# TactSwitch_v2_SCH.net
KiCad netlist of a schematic drawn in Altium Designer
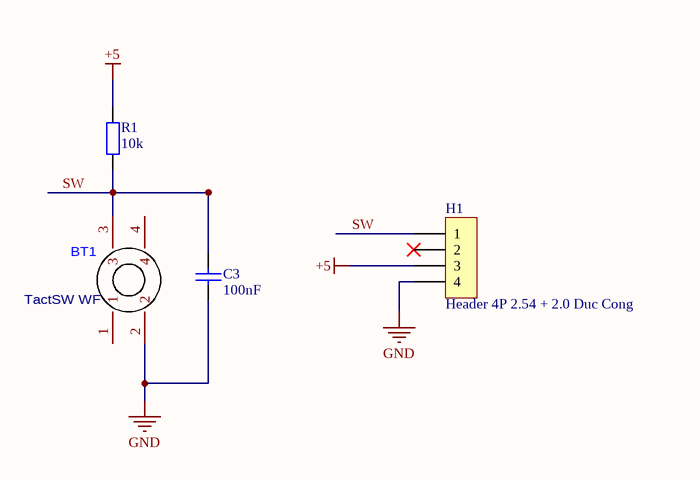
[diagram p0: TactSwitch_v2_SCH.SchDoc]

(export (version "E")
  (design (tool "Eeschema 10.0.6"))
  (components
    (comp (ref "BT1")
      (value "TactSW WF")
      (footprint "12X12 BUTTOM red")
      (description "WaterProof TactSW")
      (libsource (lib "namnt_Lib") (part "Nut Nhan 4 chan 12x12"))
    )
    (comp (ref "C3")
      (value "100nF")
      (footprint "tu 0603")
      (description "Dán")
      (libsource (lib "namnt_Lib") (part "Tu 0603 104 50V 10%"))
    )
    (comp (ref "H1")
      (value "Header 4P 2.54 + 2.0 Duc Cong")
      (footprint "Header 4P DC 2.54 + 2.0")
      (description "Cắm")
      (libsource (lib "namnt_Lib") (part "Header 4P 2.54 + 2.0 Duc Cong"))
    )
    (comp (ref "R1")
      (value "10k")
      (footprint "tro smd 0603")
      (description "Dán")
      (libsource (lib "namnt_Lib") (part "Tro 0603 1% 10k"))
    )
  )
  (nets
    (net (code "1") (name "+5") (class "Default")
      (node (ref "H1") (pin "3") (pinfunction "3_3") (pintype "passive"))
      (node (ref "R1") (pin "2") (pinfunction "2_2") (pintype "passive"))
    )
    (net (code "2") (name "/SW") (class "Default")
      (node (ref "BT1") (pin "3") (pinfunction "3_3") (pintype "passive"))
      (node (ref "C3") (pin "1") (pinfunction "1_1") (pintype "passive"))
      (node (ref "H1") (pin "1") (pinfunction "1_1") (pintype "passive"))
      (node (ref "R1") (pin "1") (pinfunction "1_1") (pintype "passive"))
    )
    (net (code "3") (name "GND") (class "Default")
      (node (ref "BT1") (pin "2") (pinfunction "2_2") (pintype "passive"))
      (node (ref "C3") (pin "2") (pinfunction "2_2") (pintype "passive"))
      (node (ref "H1") (pin "4") (pinfunction "4_4") (pintype "passive"))
    )
    (net (code "4") (name "unconnected-(BT1-Pad1)") (class "Default")
      (node (ref "BT1") (pin "1") (pinfunction "1_1") (pintype "passive"))
    )
    (net (code "5") (name "unconnected-(BT1-Pad4)") (class "Default")
      (node (ref "BT1") (pin "4") (pinfunction "4_4") (pintype "passive"))
    )
    (net (code "6") (name "unconnected-(H1-Pad2)") (class "Default")
      (node (ref "H1") (pin "2") (pinfunction "2_2") (pintype "passive+no_connect"))
    )
  )
)
